# OMD_CAN.net
KiCad netlist of a schematic drawn in Altium Designer
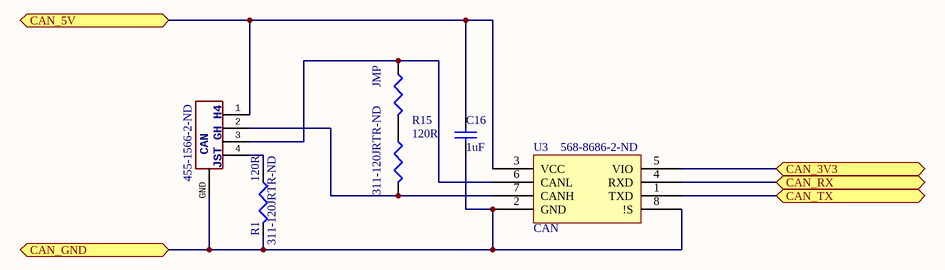
[diagram p0: OMD_CAN.SchDoc]

(export (version "E")
  (design (tool "Eeschema 10.0.6"))
  (components
    (comp (ref "C16")
      (value "1uF")
      (footprint "CAPC1005L")
      (description "CAP CER 1UF 6.3V X5R 0402")
      (fields (field (name "Comment") "Cap"))
      (libsource (lib "OMD") (part "Cap"))
    )
    (comp (ref "CAN")
      (value "JST_GH_H4")
      (footprint "JST_GH_H4")
      (description "SM04B-GHS-TB")
      (fields (field (name "SUPPLIER PART NUMBER 1") "455-1566-2-ND"))
      (libsource (lib "OMD") (part "JST_GH_H4"))
    )
    (comp (ref "JMP") (value "solder") (footprint "R0402") (libsource (lib "OMD") (part "Resistor")))
    (comp (ref "R1")
      (value "120R")
      (footprint "R0402")
      (description "RES SMD 120 OHM 5% 1/16W 0402")
      (fields (field (name "SUPPLIER PART NUMBER 1") "311-120JRTR-ND"))
      (libsource (lib "OMD") (part "Resistor"))
    )
    (comp (ref "R15")
      (value "120R")
      (footprint "R0402")
      (description "RES SMD 120 OHM 5% 1/16W 0402")
      (fields (field (name "SUPPLIER PART NUMBER 1") "311-120JRTR-ND"))
      (libsource (lib "OMD") (part "Resistor"))
    )
    (comp (ref "U3")
      (value "CAN")
      (footprint "SON65P300X100_HS-9N")
      (fields (field (name "SUPPLIER PART NUMBER 1") "568-8686-2-ND"))
      (libsource (lib "OMD") (part "CAN"))
    )
  )
  (nets
    (net (code "1") (name "/CAN_3V3") (class "Default")
      (node (ref "U3") (pin "5") (pinfunction "VIO_5") (pintype "passive"))
    )
    (net (code "2") (name "/CAN_5V") (class "Default")
      (node (ref "C16") (pin "2") (pinfunction "2_2") (pintype "passive"))
      (node (ref "CAN") (pin "1") (pinfunction "1_1") (pintype "passive"))
      (node (ref "U3") (pin "3") (pinfunction "VCC_3") (pintype "passive"))
    )
    (net (code "3") (name "/CAN_GND") (class "Default")
      (node (ref "C16") (pin "1") (pinfunction "1_1") (pintype "passive"))
      (node (ref "CAN") (pin "GND") (pinfunction "GND_GND") (pintype "passive"))
      (node (ref "R1") (pin "2") (pinfunction "2_2") (pintype "passive"))
      (node (ref "U3") (pin "2") (pinfunction "GND_2") (pintype "passive"))
      (node (ref "U3") (pin "8") (pinfunction "!S_8") (pintype "passive"))
    )
    (net (code "4") (name "/CAN_RX") (class "Default")
      (node (ref "U3") (pin "4") (pinfunction "RXD_4") (pintype "passive"))
    )
    (net (code "5") (name "/CAN_TX") (class "Default")
      (node (ref "U3") (pin "1") (pinfunction "TXD_1") (pintype "passive"))
    )
    (net (code "6") (name "Net-(CAN-Pad4)") (class "Default")
      (node (ref "CAN") (pin "4") (pinfunction "4_4") (pintype "passive"))
      (node (ref "R1") (pin "1") (pinfunction "1_1") (pintype "passive"))
    )
    (net (code "7") (name "Net-(JMP-Pad2)") (class "Default")
      (node (ref "JMP") (pin "2") (pinfunction "2_2") (pintype "passive"))
      (node (ref "R15") (pin "1") (pinfunction "1_1") (pintype "passive"))
    )
    (net (code "8") (name "Net-(U3-CANH)") (class "Default")
      (node (ref "CAN") (pin "2") (pinfunction "2_2") (pintype "passive"))
      (node (ref "R15") (pin "2") (pinfunction "2_2") (pintype "passive"))
      (node (ref "U3") (pin "7") (pinfunction "CANH_7") (pintype "passive"))
    )
    (net (code "9") (name "Net-(U3-CANL)") (class "Default")
      (node (ref "CAN") (pin "3") (pinfunction "3_3") (pintype "passive"))
      (node (ref "JMP") (pin "1") (pinfunction "1_1") (pintype "passive"))
      (node (ref "U3") (pin "6") (pinfunction "CANL_6") (pintype "passive"))
    )
  )
)
